# PAT9125_Breakout.net
KiCad netlist of a schematic drawn in EAGLE
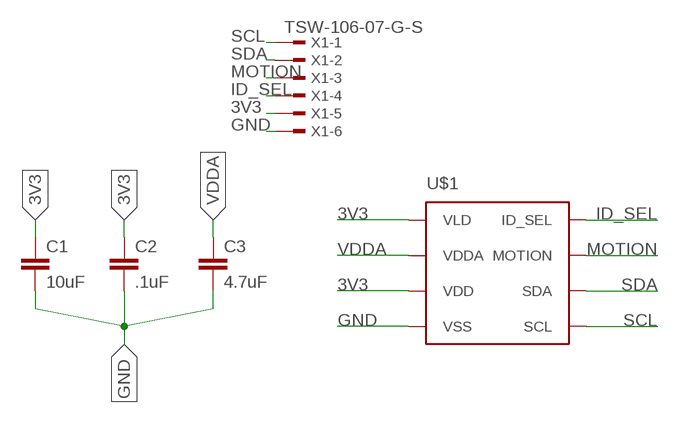
[diagram p0: schematic, sheet 1]

(export (version "E")
  (design (tool "Eeschema 10.0.6"))
  (components
    (comp (ref "C1")
      (value "10uF")
      (footprint "eagle-import:C0603")
      (libsource (lib "eagle-import") (part "C-EUC0603"))
    )
    (comp (ref "C2")
      (value ".1uF")
      (footprint "eagle-import:C0603")
      (libsource (lib "eagle-import") (part "C-EUC0603"))
    )
    (comp (ref "C3")
      (value "4.7uF")
      (footprint "eagle-import:C0603")
      (libsource (lib "eagle-import") (part "C-EUC0603"))
    )
    (comp (ref "U$1")
      (value "PAT9125EL")
      (footprint "eagle-import:PAT9125EL")
      (libsource (lib "eagle-import") (part "PAT9125EL"))
    )
    (comp (ref "X1")
      (value "TSW-106-07-G-S")
      (footprint "eagle-import:TSW-106-XX-G-S")
      (fields (field (name "MF") "Samtec Inc."))
      (libsource (lib "eagle-import") (part "TSW-106--G-S07"))
    )
  )
  (nets
    (net (code "1") (name "/ID_SEL") (class "Default")
      (node (ref "U$1") (pin "P$8") (pinfunction "ID_SEL_P$8") (pintype "input"))
      (node (ref "X1") (pin "4") (pinfunction "1_4") (pintype "passive"))
    )
    (net (code "2") (name "/MOTION") (class "Default")
      (node (ref "U$1") (pin "P$7") (pinfunction "MOTION_P$7") (pintype "input"))
      (node (ref "X1") (pin "3") (pinfunction "1_3") (pintype "passive"))
    )
    (net (code "3") (name "/SCL") (class "Default")
      (node (ref "U$1") (pin "P$5") (pinfunction "SCL_P$5") (pintype "input"))
      (node (ref "X1") (pin "1") (pinfunction "1_1") (pintype "passive"))
    )
    (net (code "4") (name "/SDA") (class "Default")
      (node (ref "U$1") (pin "P$6") (pinfunction "SDA_P$6") (pintype "input"))
      (node (ref "X1") (pin "2") (pinfunction "1_2") (pintype "passive"))
    )
    (net (code "5") (name "3V3") (class "Default")
      (node (ref "C1") (pin "1") (pinfunction "1_1") (pintype "passive"))
      (node (ref "C2") (pin "1") (pinfunction "1_1") (pintype "passive"))
      (node (ref "U$1") (pin "P$1") (pinfunction "VLD_P$1") (pintype "bidirectional"))
      (node (ref "U$1") (pin "P$3") (pinfunction "VDD_P$3") (pintype "bidirectional"))
      (node (ref "X1") (pin "5") (pinfunction "1_5") (pintype "passive"))
    )
    (net (code "6") (name "GND") (class "Default")
      (node (ref "C1") (pin "2") (pinfunction "2_2") (pintype "passive"))
      (node (ref "C2") (pin "2") (pinfunction "2_2") (pintype "passive"))
      (node (ref "C3") (pin "2") (pinfunction "2_2") (pintype "passive"))
      (node (ref "U$1") (pin "P$4") (pinfunction "VSS_P$4") (pintype "bidirectional"))
      (node (ref "X1") (pin "6") (pinfunction "1_6") (pintype "passive"))
    )
    (net (code "7") (name "VDDA") (class "Default")
      (node (ref "C3") (pin "1") (pinfunction "1_1") (pintype "passive"))
      (node (ref "U$1") (pin "P$2") (pinfunction "VDDA_P$2") (pintype "bidirectional"))
    )
  )
)
